# bot_schem_rev10.net
KiCad netlist of a schematic drawn in Altium Designer
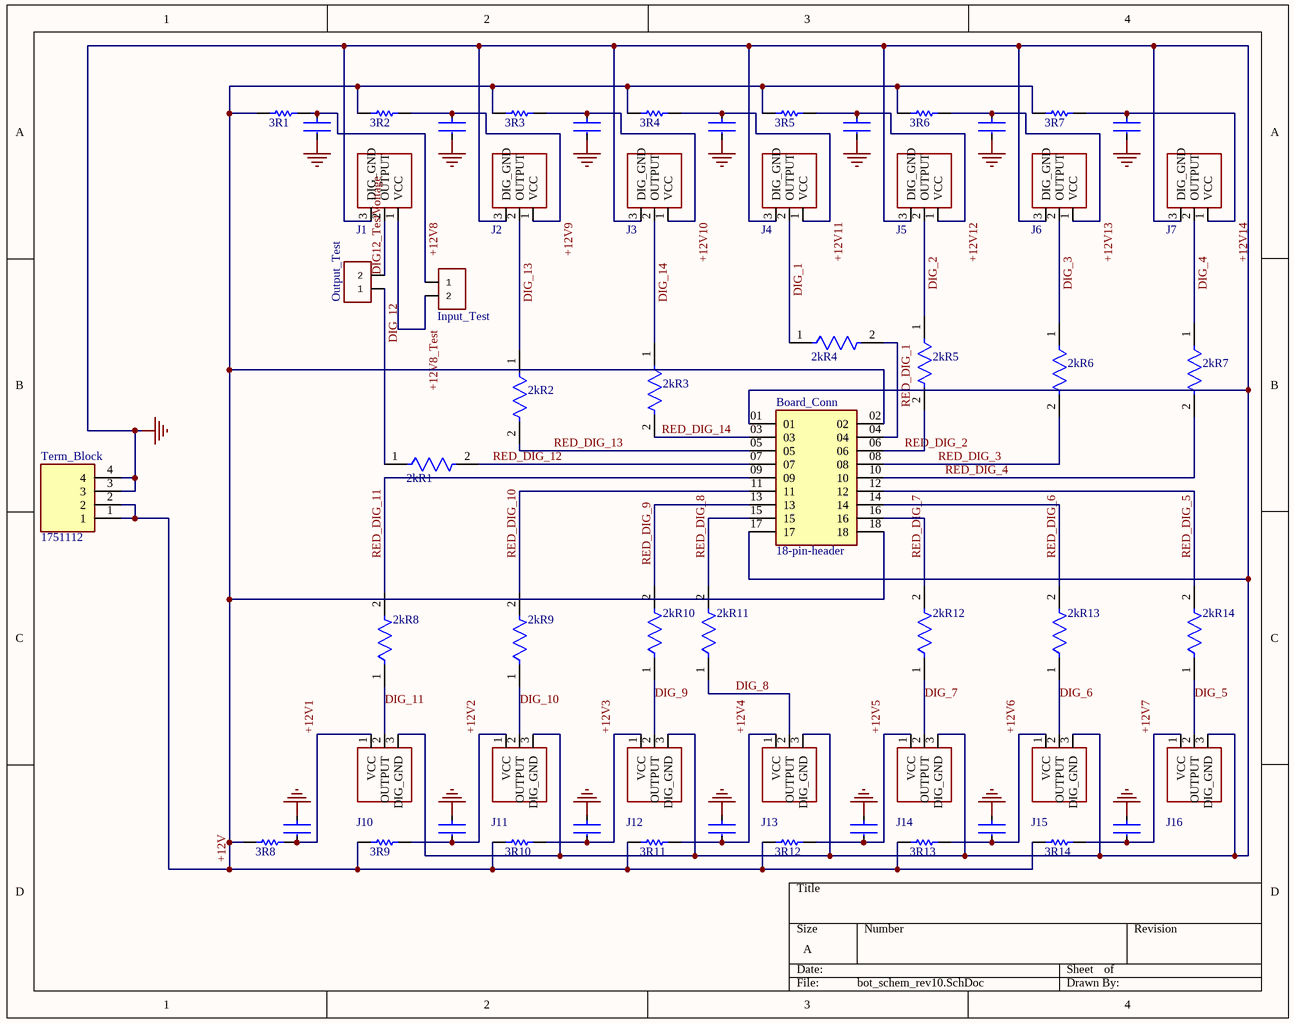
[diagram p0: bot_schem_rev10.SchDoc]

(export (version "E")
  (design (tool "Eeschema 10.0.6"))
  (components
    (comp (ref "2kR1")
      (value "CRCW06031K80FKEA")
      (footprint "2kOhm")
      (description "Res Thick Film 0603 1.8K Ohm 1% 1/10W ±100ppm/°C Molded SMD Paper T/R")
      (fields (field (name "MANUFACTURER") "Vishay") (field (name "TOLERANCE") "1%"))
      (libsource (lib "ps_schlib") (part "CRCW06031K80FKEA"))
    )
    (comp (ref "2kR2")
      (value "CRCW06031K80FKEA")
      (footprint "2kOhm")
      (description "Res Thick Film 0603 1.8K Ohm 1% 1/10W ±100ppm/°C Molded SMD Paper T/R")
      (fields (field (name "MANUFACTURER") "Vishay") (field (name "TOLERANCE") "1%"))
      (libsource (lib "ps_schlib") (part "CRCW06031K80FKEA"))
    )
    (comp (ref "2kR3")
      (value "CRCW06031K80FKEA")
      (footprint "2kOhm")
      (description "Res Thick Film 0603 1.8K Ohm 1% 1/10W ±100ppm/°C Molded SMD Paper T/R")
      (fields (field (name "MANUFACTURER") "Vishay") (field (name "TOLERANCE") "1%"))
      (libsource (lib "ps_schlib") (part "CRCW06031K80FKEA"))
    )
    (comp (ref "2kR4")
      (value "CRCW06031K80FKEA")
      (footprint "2kOhm")
      (description "Res Thick Film 0603 1.8K Ohm 1% 1/10W ±100ppm/°C Molded SMD Paper T/R")
      (fields (field (name "MANUFACTURER") "Vishay") (field (name "TOLERANCE") "1%"))
      (libsource (lib "ps_schlib") (part "CRCW06031K80FKEA"))
    )
    (comp (ref "2kR5")
      (value "CRCW06031K80FKEA")
      (footprint "2kOhm")
      (description "Res Thick Film 0603 1.8K Ohm 1% 1/10W ±100ppm/°C Molded SMD Paper T/R")
      (fields (field (name "MANUFACTURER") "Vishay") (field (name "TOLERANCE") "1%"))
      (libsource (lib "ps_schlib") (part "CRCW06031K80FKEA"))
    )
    (comp (ref "2kR6")
      (value "CRCW06031K80FKEA")
      (footprint "2kOhm")
      (description "Res Thick Film 0603 1.8K Ohm 1% 1/10W ±100ppm/°C Molded SMD Paper T/R")
      (fields (field (name "MANUFACTURER") "Vishay") (field (name "TOLERANCE") "1%"))
      (libsource (lib "ps_schlib") (part "CRCW06031K80FKEA"))
    )
    (comp (ref "2kR7")
      (value "CRCW06031K80FKEA")
      (footprint "2kOhm")
      (description "Res Thick Film 0603 1.8K Ohm 1% 1/10W ±100ppm/°C Molded SMD Paper T/R")
      (fields (field (name "MANUFACTURER") "Vishay") (field (name "TOLERANCE") "1%"))
      (libsource (lib "ps_schlib") (part "CRCW06031K80FKEA"))
    )
    (comp (ref "2kR8")
      (value "CRCW06031K80FKEA")
      (footprint "2kOhm")
      (description "Res Thick Film 0603 1.8K Ohm 1% 1/10W ±100ppm/°C Molded SMD Paper T/R")
      (fields (field (name "MANUFACTURER") "Vishay") (field (name "TOLERANCE") "1%"))
      (libsource (lib "ps_schlib") (part "CRCW06031K80FKEA"))
    )
    (comp (ref "2kR9")
      (value "CRCW06031K80FKEA")
      (footprint "2kOhm")
      (description "Res Thick Film 0603 1.8K Ohm 1% 1/10W ±100ppm/°C Molded SMD Paper T/R")
      (fields (field (name "MANUFACTURER") "Vishay") (field (name "TOLERANCE") "1%"))
      (libsource (lib "ps_schlib") (part "CRCW06031K80FKEA"))
    )
    (comp (ref "2kR10")
      (value "CRCW06031K80FKEA")
      (footprint "2kOhm")
      (description "Res Thick Film 0603 1.8K Ohm 1% 1/10W ±100ppm/°C Molded SMD Paper T/R")
      (fields (field (name "MANUFACTURER") "Vishay") (field (name "TOLERANCE") "1%"))
      (libsource (lib "ps_schlib") (part "CRCW06031K80FKEA"))
    )
    (comp (ref "2kR11")
      (value "CRCW06031K80FKEA")
      (footprint "2kOhm")
      (description "Res Thick Film 0603 1.8K Ohm 1% 1/10W ±100ppm/°C Molded SMD Paper T/R")
      (fields (field (name "MANUFACTURER") "Vishay") (field (name "TOLERANCE") "1%"))
      (libsource (lib "ps_schlib") (part "CRCW06031K80FKEA"))
    )
    (comp (ref "2kR12")
      (value "CRCW06031K80FKEA")
      (footprint "2kOhm")
      (description "Res Thick Film 0603 1.8K Ohm 1% 1/10W ±100ppm/°C Molded SMD Paper T/R")
      (fields (field (name "MANUFACTURER") "Vishay") (field (name "TOLERANCE") "1%"))
      (libsource (lib "ps_schlib") (part "CRCW06031K80FKEA"))
    )
    (comp (ref "2kR13")
      (value "CRCW06031K80FKEA")
      (footprint "2kOhm")
      (description "Res Thick Film 0603 1.8K Ohm 1% 1/10W ±100ppm/°C Molded SMD Paper T/R")
      (fields (field (name "MANUFACTURER") "Vishay") (field (name "TOLERANCE") "1%"))
      (libsource (lib "ps_schlib") (part "CRCW06031K80FKEA"))
    )
    (comp (ref "2kR14")
      (value "CRCW06031K80FKEA")
      (footprint "2kOhm")
      (description "Res Thick Film 0603 1.8K Ohm 1% 1/10W ±100ppm/°C Molded SMD Paper T/R")
      (fields (field (name "MANUFACTURER") "Vishay") (field (name "TOLERANCE") "1%"))
      (libsource (lib "ps_schlib") (part "CRCW06031K80FKEA"))
    )
    (comp (ref "3R1")
      (value "ERJ-2BQJR30X")
      (footprint "03 Ohm")
      (description "RES 0.3 OHM 5% 1/6W 0402")
      (fields (field (name "MANUFACTURER") "Panasonic") (field (name "TOLERANCE") "5%"))
      (libsource (lib "ps_schlib") (part "ERJ-2BQJR30X"))
    )
    (comp (ref "3R2")
      (value "ERJ-2BQJR30X")
      (footprint "03 Ohm")
      (description "RES 0.3 OHM 5% 1/6W 0402")
      (fields (field (name "MANUFACTURER") "Panasonic") (field (name "TOLERANCE") "5%"))
      (libsource (lib "ps_schlib") (part "ERJ-2BQJR30X"))
    )
    (comp (ref "3R3")
      (value "ERJ-2BQJR30X")
      (footprint "03 Ohm")
      (description "RES 0.3 OHM 5% 1/6W 0402")
      (fields (field (name "MANUFACTURER") "Panasonic") (field (name "TOLERANCE") "5%"))
      (libsource (lib "ps_schlib") (part "ERJ-2BQJR30X"))
    )
    (comp (ref "3R4")
      (value "ERJ-2BQJR30X")
      (footprint "03 Ohm")
      (description "RES 0.3 OHM 5% 1/6W 0402")
      (fields (field (name "MANUFACTURER") "Panasonic") (field (name "TOLERANCE") "5%"))
      (libsource (lib "ps_schlib") (part "ERJ-2BQJR30X"))
    )
    (comp (ref "3R5")
      (value "ERJ-2BQJR30X")
      (footprint "03 Ohm")
      (description "RES 0.3 OHM 5% 1/6W 0402")
      (fields (field (name "MANUFACTURER") "Panasonic") (field (name "TOLERANCE") "5%"))
      (libsource (lib "ps_schlib") (part "ERJ-2BQJR30X"))
    )
    (comp (ref "3R6")
      (value "ERJ-2BQJR30X")
      (footprint "03 Ohm")
      (description "RES 0.3 OHM 5% 1/6W 0402")
      (fields (field (name "MANUFACTURER") "Panasonic") (field (name "TOLERANCE") "5%"))
      (libsource (lib "ps_schlib") (part "ERJ-2BQJR30X"))
    )
    (comp (ref "3R7")
      (value "ERJ-2BQJR30X")
      (footprint "03 Ohm")
      (description "RES 0.3 OHM 5% 1/6W 0402")
      (fields (field (name "MANUFACTURER") "Panasonic") (field (name "TOLERANCE") "5%"))
      (libsource (lib "ps_schlib") (part "ERJ-2BQJR30X"))
    )
    (comp (ref "3R8")
      (value "ERJ-2BQJR30X")
      (footprint "03 Ohm")
      (description "RES 0.3 OHM 5% 1/6W 0402")
      (fields (field (name "MANUFACTURER") "Panasonic") (field (name "TOLERANCE") "5%"))
      (libsource (lib "ps_schlib") (part "ERJ-2BQJR30X"))
    )
    (comp (ref "3R9")
      (value "ERJ-2BQJR30X")
      (footprint "03 Ohm")
      (description "RES 0.3 OHM 5% 1/6W 0402")
      (fields (field (name "MANUFACTURER") "Panasonic") (field (name "TOLERANCE") "5%"))
      (libsource (lib "ps_schlib") (part "ERJ-2BQJR30X"))
    )
    (comp (ref "3R10")
      (value "ERJ-2BQJR30X")
      (footprint "03 Ohm")
      (description "RES 0.3 OHM 5% 1/6W 0402")
      (fields (field (name "MANUFACTURER") "Panasonic") (field (name "TOLERANCE") "5%"))
      (libsource (lib "ps_schlib") (part "ERJ-2BQJR30X"))
    )
    (comp (ref "3R11")
      (value "ERJ-2BQJR30X")
      (footprint "03 Ohm")
      (description "RES 0.3 OHM 5% 1/6W 0402")
      (fields (field (name "MANUFACTURER") "Panasonic") (field (name "TOLERANCE") "5%"))
      (libsource (lib "ps_schlib") (part "ERJ-2BQJR30X"))
    )
    (comp (ref "3R12")
      (value "ERJ-2BQJR30X")
      (footprint "03 Ohm")
      (description "RES 0.3 OHM 5% 1/6W 0402")
      (fields (field (name "MANUFACTURER") "Panasonic") (field (name "TOLERANCE") "5%"))
      (libsource (lib "ps_schlib") (part "ERJ-2BQJR30X"))
    )
    (comp (ref "3R13")
      (value "ERJ-2BQJR30X")
      (footprint "03 Ohm")
      (description "RES 0.3 OHM 5% 1/6W 0402")
      (fields (field (name "MANUFACTURER") "Panasonic") (field (name "TOLERANCE") "5%"))
      (libsource (lib "ps_schlib") (part "ERJ-2BQJR30X"))
    )
    (comp (ref "3R14")
      (value "ERJ-2BQJR30X")
      (footprint "03 Ohm")
      (description "RES 0.3 OHM 5% 1/6W 0402")
      (fields (field (name "MANUFACTURER") "Panasonic") (field (name "TOLERANCE") "5%"))
      (libsource (lib "ps_schlib") (part "ERJ-2BQJR30X"))
    )
    (comp (ref "Board_Conn")
      (value "18-pin-header")
      (footprint "18 pin header")
      (libsource (lib "bot_schlib") (part "18-pin-header"))
    )
    (comp (ref "C1")
      (value "C0805C104K5RACTU")
      (footprint "100nF")
      (description "Cap Ceramic 0.1uF 50V X7R 10% SMD 2.0 x 1.2 mm 125 C Paper T/R")
      (fields (field (name "MANUFACTURER") "KEMET") (field (name "TOLERANCE") "10%"))
      (libsource (lib "ps_schlib") (part "C0805C104K5RACTU"))
    )
    (comp (ref "C2")
      (value "C0805C104K5RACTU")
      (footprint "100nF")
      (description "Cap Ceramic 0.1uF 50V X7R 10% SMD 2.0 x 1.2 mm 125 C Paper T/R")
      (fields (field (name "MANUFACTURER") "KEMET") (field (name "TOLERANCE") "10%"))
      (libsource (lib "ps_schlib") (part "C0805C104K5RACTU"))
    )
    (comp (ref "C3")
      (value "C0805C104K5RACTU")
      (footprint "100nF")
      (description "Cap Ceramic 0.1uF 50V X7R 10% SMD 2.0 x 1.2 mm 125 C Paper T/R")
      (fields (field (name "MANUFACTURER") "KEMET") (field (name "TOLERANCE") "10%"))
      (libsource (lib "ps_schlib") (part "C0805C104K5RACTU"))
    )
    (comp (ref "C4")
      (value "C0805C104K5RACTU")
      (footprint "100nF")
      (description "Cap Ceramic 0.1uF 50V X7R 10% SMD 2.0 x 1.2 mm 125 C Paper T/R")
      (fields (field (name "MANUFACTURER") "KEMET") (field (name "TOLERANCE") "10%"))
      (libsource (lib "ps_schlib") (part "C0805C104K5RACTU"))
    )
    (comp (ref "C5")
      (value "C0805C104K5RACTU")
      (footprint "100nF")
      (description "Cap Ceramic 0.1uF 50V X7R 10% SMD 2.0 x 1.2 mm 125 C Paper T/R")
      (fields (field (name "MANUFACTURER") "KEMET") (field (name "TOLERANCE") "10%"))
      (libsource (lib "ps_schlib") (part "C0805C104K5RACTU"))
    )
    (comp (ref "C6")
      (value "C0805C104K5RACTU")
      (footprint "100nF")
      (description "Cap Ceramic 0.1uF 50V X7R 10% SMD 2.0 x 1.2 mm 125 C Paper T/R")
      (fields (field (name "MANUFACTURER") "KEMET") (field (name "TOLERANCE") "10%"))
      (libsource (lib "ps_schlib") (part "C0805C104K5RACTU"))
    )
    (comp (ref "C7")
      (value "C0805C104K5RACTU")
      (footprint "100nF")
      (description "Cap Ceramic 0.1uF 50V X7R 10% SMD 2.0 x 1.2 mm 125 C Paper T/R")
      (fields (field (name "MANUFACTURER") "KEMET") (field (name "TOLERANCE") "10%"))
      (libsource (lib "ps_schlib") (part "C0805C104K5RACTU"))
    )
    (comp (ref "C8")
      (value "C0805C104K5RACTU")
      (footprint "100nF")
      (description "Cap Ceramic 0.1uF 50V X7R 10% SMD 2.0 x 1.2 mm 125 C Paper T/R")
      (fields (field (name "MANUFACTURER") "KEMET") (field (name "TOLERANCE") "10%"))
      (libsource (lib "ps_schlib") (part "C0805C104K5RACTU"))
    )
    (comp (ref "C9")
      (value "C0805C104K5RACTU")
      (footprint "100nF")
      (description "Cap Ceramic 0.1uF 50V X7R 10% SMD 2.0 x 1.2 mm 125 C Paper T/R")
      (fields (field (name "MANUFACTURER") "KEMET") (field (name "TOLERANCE") "10%"))
      (libsource (lib "ps_schlib") (part "C0805C104K5RACTU"))
    )
    (comp (ref "C10")
      (value "C0805C104K5RACTU")
      (footprint "100nF")
      (description "Cap Ceramic 0.1uF 50V X7R 10% SMD 2.0 x 1.2 mm 125 C Paper T/R")
      (fields (field (name "MANUFACTURER") "KEMET") (field (name "TOLERANCE") "10%"))
      (libsource (lib "ps_schlib") (part "C0805C104K5RACTU"))
    )
    (comp (ref "C11")
      (value "C0805C104K5RACTU")
      (footprint "100nF")
      (description "Cap Ceramic 0.1uF 50V X7R 10% SMD 2.0 x 1.2 mm 125 C Paper T/R")
      (fields (field (name "MANUFACTURER") "KEMET") (field (name "TOLERANCE") "10%"))
      (libsource (lib "ps_schlib") (part "C0805C104K5RACTU"))
    )
    (comp (ref "C12")
      (value "C0805C104K5RACTU")
      (footprint "100nF")
      (description "Cap Ceramic 0.1uF 50V X7R 10% SMD 2.0 x 1.2 mm 125 C Paper T/R")
      (fields (field (name "MANUFACTURER") "KEMET") (field (name "TOLERANCE") "10%"))
      (libsource (lib "ps_schlib") (part "C0805C104K5RACTU"))
    )
    (comp (ref "C13")
      (value "C0805C104K5RACTU")
      (footprint "100nF")
      (description "Cap Ceramic 0.1uF 50V X7R 10% SMD 2.0 x 1.2 mm 125 C Paper T/R")
      (fields (field (name "MANUFACTURER") "KEMET") (field (name "TOLERANCE") "10%"))
      (libsource (lib "ps_schlib") (part "C0805C104K5RACTU"))
    )
    (comp (ref "C14")
      (value "C0805C104K5RACTU")
      (footprint "100nF")
      (description "Cap Ceramic 0.1uF 50V X7R 10% SMD 2.0 x 1.2 mm 125 C Paper T/R")
      (fields (field (name "MANUFACTURER") "KEMET") (field (name "TOLERANCE") "10%"))
      (libsource (lib "ps_schlib") (part "C0805C104K5RACTU"))
    )
    (comp (ref "Input_Test")
      (value "PRPC001DFAN-RC")
      (footprint "PRPC001DFAN-RC")
      (description "Conn Header Vert 2POS")
      (fields (field (name "MANUFACTURER") "Sullins"))
      (libsource (lib "ps_schlib") (part "PRPC001DFAN-RC"))
    )
    (comp (ref "J1")
      (value "IF-D95T")
      (footprint "IF-D95")
      (description "DETECTOR PHOTOLOGIC TTL/CMOS")
      (fields (field (name "MANUFACTURER") "Industrial Fiber Optics"))
      (libsource (lib "ps_schlib") (part "IF-D95T"))
    )
    (comp (ref "J2")
      (value "IF-D95T")
      (footprint "IF-D95")
      (description "DETECTOR PHOTOLOGIC TTL/CMOS")
      (fields (field (name "MANUFACTURER") "Industrial Fiber Optics"))
      (libsource (lib "ps_schlib") (part "IF-D95T"))
    )
    (comp (ref "J3")
      (value "IF-D95T")
      (footprint "IF-D95")
      (description "DETECTOR PHOTOLOGIC TTL/CMOS")
      (fields (field (name "MANUFACTURER") "Industrial Fiber Optics"))
      (libsource (lib "ps_schlib") (part "IF-D95T"))
    )
    (comp (ref "J4")
      (value "IF-D95T")
      (footprint "IF-D95")
      (description "DETECTOR PHOTOLOGIC TTL/CMOS")
      (fields (field (name "MANUFACTURER") "Industrial Fiber Optics"))
      (libsource (lib "ps_schlib") (part "IF-D95T"))
    )
    (comp (ref "J5")
      (value "IF-D95T")
      (footprint "IF-D95")
      (description "DETECTOR PHOTOLOGIC TTL/CMOS")
      (fields (field (name "MANUFACTURER") "Industrial Fiber Optics"))
      (libsource (lib "ps_schlib") (part "IF-D95T"))
    )
    (comp (ref "J6")
      (value "IF-D95T")
      (footprint "IF-D95")
      (description "DETECTOR PHOTOLOGIC TTL/CMOS")
      (fields (field (name "MANUFACTURER") "Industrial Fiber Optics"))
      (libsource (lib "ps_schlib") (part "IF-D95T"))
    )
    (comp (ref "J7")
      (value "IF-D95T")
      (footprint "IF-D95")
      (description "DETECTOR PHOTOLOGIC TTL/CMOS")
      (fields (field (name "MANUFACTURER") "Industrial Fiber Optics"))
      (libsource (lib "ps_schlib") (part "IF-D95T"))
    )
    (comp (ref "J10")
      (value "IF-D95T")
      (footprint "IF-D95")
      (description "DETECTOR PHOTOLOGIC TTL/CMOS")
      (fields (field (name "MANUFACTURER") "Industrial Fiber Optics"))
      (libsource (lib "ps_schlib") (part "IF-D95T"))
    )
    (comp (ref "J11")
      (value "IF-D95T")
      (footprint "IF-D95")
      (description "DETECTOR PHOTOLOGIC TTL/CMOS")
      (fields (field (name "MANUFACTURER") "Industrial Fiber Optics"))
      (libsource (lib "ps_schlib") (part "IF-D95T"))
    )
    (comp (ref "J12")
      (value "IF-D95T")
      (footprint "IF-D95")
      (description "DETECTOR PHOTOLOGIC TTL/CMOS")
      (fields (field (name "MANUFACTURER") "Industrial Fiber Optics"))
      (libsource (lib "ps_schlib") (part "IF-D95T"))
    )
    (comp (ref "J13")
      (value "IF-D95T")
      (footprint "IF-D95")
      (description "DETECTOR PHOTOLOGIC TTL/CMOS")
      (fields (field (name "MANUFACTURER") "Industrial Fiber Optics"))
      (libsource (lib "ps_schlib") (part "IF-D95T"))
    )
    (comp (ref "J14")
      (value "IF-D95T")
      (footprint "IF-D95")
      (description "DETECTOR PHOTOLOGIC TTL/CMOS")
      (fields (field (name "MANUFACTURER") "Industrial Fiber Optics"))
      (libsource (lib "ps_schlib") (part "IF-D95T"))
    )
    (comp (ref "J15")
      (value "IF-D95T")
      (footprint "IF-D95")
      (description "DETECTOR PHOTOLOGIC TTL/CMOS")
      (fields (field (name "MANUFACTURER") "Industrial Fiber Optics"))
      (libsource (lib "ps_schlib") (part "IF-D95T"))
    )
    (comp (ref "J16")
      (value "IF-D95T")
      (footprint "IF-D95")
      (description "DETECTOR PHOTOLOGIC TTL/CMOS")
      (fields (field (name "MANUFACTURER") "Industrial Fiber Optics"))
      (libsource (lib "ps_schlib") (part "IF-D95T"))
    )
    (comp (ref "Output_Test")
      (value "PRPC001DFAN-RC")
      (footprint "PRPC001DFAN-RC")
      (description "Conn Header Vert 2POS")
      (fields (field (name "MANUFACTURER") "Sullins"))
      (libsource (lib "ps_schlib") (part "PRPC001DFAN-RC"))
    )
    (comp (ref "Term_Block")
      (value "1751112")
      (footprint "SamacSys:1751112")
      (description "Connector")
      (libsource (lib "*") (part "1751112"))
    )
  )
  (nets
    (net (code "1") (name "/+12V") (class "Default")
      (node (ref "3R1") (pin "1") (pinfunction "1_1") (pintype "passive"))
      (node (ref "3R10") (pin "1") (pinfunction "1_1") (pintype "passive"))
      (node (ref "3R11") (pin "1") (pinfunction "1_1") (pintype "passive"))
      (node (ref "3R12") (pin "1") (pinfunction "1_1") (pintype "passive"))
      (node (ref "3R13") (pin "1") (pinfunction "1_1") (pintype "passive"))
      (node (ref "3R14") (pin "1") (pinfunction "1_1") (pintype "passive"))
      (node (ref "3R2") (pin "1") (pinfunction "1_1") (pintype "passive"))
      (node (ref "3R3") (pin "1") (pinfunction "1_1") (pintype "passive"))
      (node (ref "3R4") (pin "1") (pinfunction "1_1") (pintype "passive"))
      (node (ref "3R5") (pin "1") (pinfunction "1_1") (pintype "passive"))
      (node (ref "3R6") (pin "1") (pinfunction "1_1") (pintype "passive"))
      (node (ref "3R7") (pin "1") (pinfunction "1_1") (pintype "passive"))
      (node (ref "3R8") (pin "1") (pinfunction "1_1") (pintype "passive"))
      (node (ref "3R9") (pin "1") (pinfunction "1_1") (pintype "passive"))
      (node (ref "Board_Conn") (pin "02") (pinfunction "02_02") (pintype "passive"))
      (node (ref "Board_Conn") (pin "18") (pinfunction "18_18") (pintype "passive"))
      (node (ref "Term_Block") (pin "1") (pinfunction "1_1") (pintype "passive"))
      (node (ref "Term_Block") (pin "2") (pinfunction "2_2") (pintype "passive"))
    )
    (net (code "2") (name "/+12V1") (class "Default")
      (node (ref "3R8") (pin "2") (pinfunction "2_2") (pintype "passive"))
      (node (ref "C8") (pin "2") (pinfunction "2_2") (pintype "passive"))
      (node (ref "J10") (pin "1") (pinfunction "VCC_1") (pintype "passive"))
    )
    (net (code "3") (name "/+12V2") (class "Default")
      (node (ref "3R9") (pin "2") (pinfunction "2_2") (pintype "passive"))
      (node (ref "C9") (pin "2") (pinfunction "2_2") (pintype "passive"))
      (node (ref "J11") (pin "1") (pinfunction "VCC_1") (pintype "passive"))
    )
    (net (code "4") (name "/+12V3") (class "Default")
      (node (ref "3R10") (pin "2") (pinfunction "2_2") (pintype "passive"))
      (node (ref "C10") (pin "2") (pinfunction "2_2") (pintype "passive"))
      (node (ref "J12") (pin "1") (pinfunction "VCC_1") (pintype "passive"))
    )
    (net (code "5") (name "/+12V4") (class "Default")
      (node (ref "3R11") (pin "2") (pinfunction "2_2") (pintype "passive"))
      (node (ref "C11") (pin "2") (pinfunction "2_2") (pintype "passive"))
      (node (ref "J13") (pin "1") (pinfunction "VCC_1") (pintype "passive"))
    )
    (net (code "6") (name "/+12V5") (class "Default")
      (node (ref "3R12") (pin "2") (pinfunction "2_2") (pintype "passive"))
      (node (ref "C12") (pin "2") (pinfunction "2_2") (pintype "passive"))
      (node (ref "J14") (pin "1") (pinfunction "VCC_1") (pintype "passive"))
    )
    (net (code "7") (name "/+12V6") (class "Default")
      (node (ref "3R13") (pin "2") (pinfunction "2_2") (pintype "passive"))
      (node (ref "C13") (pin "2") (pinfunction "2_2") (pintype "passive"))
      (node (ref "J15") (pin "1") (pinfunction "VCC_1") (pintype "passive"))
    )
    (net (code "8") (name "/+12V7") (class "Default")
      (node (ref "3R14") (pin "2") (pinfunction "2_2") (pintype "passive"))
      (node (ref "C14") (pin "2") (pinfunction "2_2") (pintype "passive"))
      (node (ref "J16") (pin "1") (pinfunction "VCC_1") (pintype "passive"))
    )
    (net (code "9") (name "/+12V8") (class "Default")
      (node (ref "3R1") (pin "2") (pinfunction "2_2") (pintype "passive"))
      (node (ref "C1") (pin "1") (pinfunction "1_1") (pintype "passive"))
      (node (ref "Input_Test") (pin "1") (pinfunction "1_1") (pintype "passive"))
    )
    (net (code "10") (name "/+12V8_Test") (class "Default")
      (node (ref "Input_Test") (pin "2") (pinfunction "2_2") (pintype "passive"))
      (node (ref "J1") (pin "1") (pinfunction "VCC_1") (pintype "passive"))
    )
    (net (code "11") (name "/+12V9") (class "Default")
      (node (ref "3R2") (pin "2") (pinfunction "2_2") (pintype "passive"))
      (node (ref "C2") (pin "1") (pinfunction "1_1") (pintype "passive"))
      (node (ref "J2") (pin "1") (pinfunction "VCC_1") (pintype "passive"))
    )
    (net (code "12") (name "/+12V10") (class "Default")
      (node (ref "3R3") (pin "2") (pinfunction "2_2") (pintype "passive"))
      (node (ref "C3") (pin "1") (pinfunction "1_1") (pintype "passive"))
      (node (ref "J3") (pin "1") (pinfunction "VCC_1") (pintype "passive"))
    )
    (net (code "13") (name "/+12V11") (class "Default")
      (node (ref "3R4") (pin "2") (pinfunction "2_2") (pintype "passive"))
      (node (ref "C4") (pin "1") (pinfunction "1_1") (pintype "passive"))
      (node (ref "J4") (pin "1") (pinfunction "VCC_1") (pintype "passive"))
    )
    (net (code "14") (name "/+12V12") (class "Default")
      (node (ref "3R5") (pin "2") (pinfunction "2_2") (pintype "passive"))
      (node (ref "C5") (pin "1") (pinfunction "1_1") (pintype "passive"))
      (node (ref "J5") (pin "1") (pinfunction "VCC_1") (pintype "passive"))
    )
    (net (code "15") (name "/+12V13") (class "Default")
      (node (ref "3R6") (pin "2") (pinfunction "2_2") (pintype "passive"))
      (node (ref "C6") (pin "1") (pinfunction "1_1") (pintype "passive"))
      (node (ref "J6") (pin "1") (pinfunction "VCC_1") (pintype "passive"))
    )
    (net (code "16") (name "/+12V14") (class "Default")
      (node (ref "3R7") (pin "2") (pinfunction "2_2") (pintype "passive"))
      (node (ref "C7") (pin "1") (pinfunction "1_1") (pintype "passive"))
      (node (ref "J7") (pin "1") (pinfunction "VCC_1") (pintype "passive"))
    )
    (net (code "18") (name "/DIG12_TestVoltage") (class "Default")
      (node (ref "J1") (pin "2") (pinfunction "OUTPUT_2") (pintype "passive"))
      (node (ref "Output_Test") (pin "2") (pinfunction "2_2") (pintype "passive"))
    )
    (net (code "19") (name "/DIG_1") (class "Default")
      (node (ref "2kR4") (pin "1") (pinfunction "1_1") (pintype "passive"))
      (node (ref "J4") (pin "2") (pinfunction "OUTPUT_2") (pintype "passive"))
    )
    (net (code "20") (name "/DIG_2") (class "Default")
      (node (ref "2kR5") (pin "1") (pinfunction "1_1") (pintype "passive"))
      (node (ref "J5") (pin "2") (pinfunction "OUTPUT_2") (pintype "passive"))
    )
    (net (code "21") (name "/DIG_3") (class "Default")
      (node (ref "2kR6") (pin "1") (pinfunction "1_1") (pintype "passive"))
      (node (ref "J6") (pin "2") (pinfunction "OUTPUT_2") (pintype "passive"))
    )
    (net (code "22") (name "/DIG_4") (class "Default")
      (node (ref "2kR7") (pin "1") (pinfunction "1_1") (pintype "passive"))
      (node (ref "J7") (pin "2") (pinfunction "OUTPUT_2") (pintype "passive"))
    )
    (net (code "23") (name "/DIG_5") (class "Default")
      (node (ref "2kR14") (pin "1") (pinfunction "1_1") (pintype "passive"))
      (node (ref "J16") (pin "2") (pinfunction "OUTPUT_2") (pintype "passive"))
    )
    (net (code "24") (name "/DIG_6") (class "Default")
      (node (ref "2kR13") (pin "1") (pinfunction "1_1") (pintype "passive"))
      (node (ref "J15") (pin "2") (pinfunction "OUTPUT_2") (pintype "passive"))
    )
    (net (code "25") (name "/DIG_7") (class "Default")
      (node (ref "2kR12") (pin "1") (pinfunction "1_1") (pintype "passive"))
      (node (ref "J14") (pin "2") (pinfunction "OUTPUT_2") (pintype "passive"))
    )
    (net (code "26") (name "/DIG_8") (class "Default")
      (node (ref "2kR11") (pin "1") (pinfunction "1_1") (pintype "passive"))
      (node (ref "J13") (pin "2") (pinfunction "OUTPUT_2") (pintype "passive"))
    )
    (net (code "27") (name "/DIG_9") (class "Default")
      (node (ref "2kR10") (pin "1") (pinfunction "1_1") (pintype "passive"))
      (node (ref "J12") (pin "2") (pinfunction "OUTPUT_2") (pintype "passive"))
    )
    (net (code "28") (name "/DIG_10") (class "Default")
      (node (ref "2kR9") (pin "1") (pinfunction "1_1") (pintype "passive"))
      (node (ref "J11") (pin "2") (pinfunction "OUTPUT_2") (pintype "passive"))
    )
    (net (code "29") (name "/DIG_11") (class "Default")
      (node (ref "2kR8") (pin "1") (pinfunction "1_1") (pintype "passive"))
      (node (ref "J10") (pin "2") (pinfunction "OUTPUT_2") (pintype "passive"))
    )
    (net (code "30") (name "/DIG_12") (class "Default")
      (node (ref "2kR1") (pin "1") (pinfunction "1_1") (pintype "passive"))
      (node (ref "Output_Test") (pin "1") (pinfunction "1_1") (pintype "passive"))
    )
    (net (code "31") (name "/DIG_13") (class "Default")
      (node (ref "2kR2") (pin "1") (pinfunction "1_1") (pintype "passive"))
      (node (ref "J2") (pin "2") (pinfunction "OUTPUT_2") (pintype "passive"))
    )
    (net (code "32") (name "/DIG_14") (class "Default")
      (node (ref "2kR3") (pin "1") (pinfunction "1_1") (pintype "passive"))
      (node (ref "J3") (pin "2") (pinfunction "OUTPUT_2") (pintype "passive"))
    )
    (net (code "33") (name "/RED_DIG_1") (class "Default")
      (node (ref "2kR4") (pin "2") (pinfunction "2_2") (pintype "passive"))
      (node (ref "Board_Conn") (pin "04") (pinfunction "04_04") (pintype "passive"))
    )
    (net (code "34") (name "/RED_DIG_2") (class "Default")
      (node (ref "2kR5") (pin "2") (pinfunction "2_2") (pintype "passive"))
      (node (ref "Board_Conn") (pin "06") (pinfunction "06_06") (pintype "passive"))
    )
    (net (code "35") (name "/RED_DIG_3") (class "Default")
      (node (ref "2kR6") (pin "2") (pinfunction "2_2") (pintype "passive"))
      (node (ref "Board_Conn") (pin "08") (pinfunction "08_08") (pintype "passive"))
    )
    (net (code "36") (name "/RED_DIG_4") (class "Default")
      (node (ref "2kR7") (pin "2") (pinfunction "2_2") (pintype "passive"))
      (node (ref "Board_Conn") (pin "10") (pinfunction "10_10") (pintype "passive"))
    )
    (net (code "37") (name "/RED_DIG_5") (class "Default")
      (node (ref "2kR14") (pin "2") (pinfunction "2_2") (pintype "passive"))
      (node (ref "Board_Conn") (pin "12") (pinfunction "12_12") (pintype "passive"))
    )
    (net (code "38") (name "/RED_DIG_6") (class "Default")
      (node (ref "2kR13") (pin "2") (pinfunction "2_2") (pintype "passive"))
      (node (ref "Board_Conn") (pin "14") (pinfunction "14_14") (pintype "passive"))
    )
    (net (code "39") (name "/RED_DIG_7") (class "Default")
      (node (ref "2kR12") (pin "2") (pinfunction "2_2") (pintype "passive"))
      (node (ref "Board_Conn") (pin "16") (pinfunction "16_16") (pintype "passive"))
    )
    (net (code "40") (name "/RED_DIG_8") (class "Default")
      (node (ref "2kR11") (pin "2") (pinfunction "2_2") (pintype "passive"))
      (node (ref "Board_Conn") (pin "15") (pinfunction "15_15") (pintype "passive"))
    )
    (net (code "41") (name "/RED_DIG_9") (class "Default")
      (node (ref "2kR10") (pin "2") (pinfunction "2_2") (pintype "passive"))
      (node (ref "Board_Conn") (pin "13") (pinfunction "13_13") (pintype "passive"))
    )
    (net (code "42") (name "/RED_DIG_10") (class "Default")
      (node (ref "2kR9") (pin "2") (pinfunction "2_2") (pintype "passive"))
      (node (ref "Board_Conn") (pin "11") (pinfunction "11_11") (pintype "passive"))
    )
    (net (code "43") (name "/RED_DIG_11") (class "Default")
      (node (ref "2kR8") (pin "2") (pinfunction "2_2") (pintype "passive"))
      (node (ref "Board_Conn") (pin "09") (pinfunction "09_09") (pintype "passive"))
    )
    (net (code "44") (name "/RED_DIG_12") (class "Default")
      (node (ref "2kR1") (pin "2") (pinfunction "2_2") (pintype "passive"))
      (node (ref "Board_Conn") (pin "07") (pinfunction "07_07") (pintype "passive"))
    )
    (net (code "45") (name "/RED_DIG_13") (class "Default")
      (node (ref "2kR2") (pin "2") (pinfunction "2_2") (pintype "passive"))
      (node (ref "Board_Conn") (pin "05") (pinfunction "05_05") (pintype "passive"))
    )
    (net (code "46") (name "/RED_DIG_14") (class "Default")
      (node (ref "2kR3") (pin "2") (pinfunction "2_2") (pintype "passive"))
      (node (ref "Board_Conn") (pin "03") (pinfunction "03_03") (pintype "passive"))
    )
    (net (code "47") (name "GND") (class "Default")
      (node (ref "Board_Conn") (pin "01") (pinfunction "01_01") (pintype "passive"))
      (node (ref "Board_Conn") (pin "17") (pinfunction "17_17") (pintype "passive"))
      (node (ref "C1") (pin "2") (pinfunction "2_2") (pintype "passive"))
      (node (ref "C10") (pin "1") (pinfunction "1_1") (pintype "passive"))
      (node (ref "C11") (pin "1") (pinfunction "1_1") (pintype "passive"))
      (node (ref "C12") (pin "1") (pinfunction "1_1") (pintype "passive"))
      (node (ref "C13") (pin "1") (pinfunction "1_1") (pintype "passive"))
      (node (ref "C14") (pin "1") (pinfunction "1_1") (pintype "passive"))
      (node (ref "C2") (pin "2") (pinfunction "2_2") (pintype "passive"))
      (node (ref "C3") (pin "2") (pinfunction "2_2") (pintype "passive"))
      (node (ref "C4") (pin "2") (pinfunction "2_2") (pintype "passive"))
      (node (ref "C5") (pin "2") (pinfunction "2_2") (pintype "passive"))
      (node (ref "C6") (pin "2") (pinfunction "2_2") (pintype "passive"))
      (node (ref "C7") (pin "2") (pinfunction "2_2") (pintype "passive"))
      (node (ref "C8") (pin "1") (pinfunction "1_1") (pintype "passive"))
      (node (ref "C9") (pin "1") (pinfunction "1_1") (pintype "passive"))
      (node (ref "J1") (pin "3") (pinfunction "DIG_GND_3") (pintype "passive"))
      (node (ref "J10") (pin "3") (pinfunction "DIG_GND_3") (pintype "passive"))
      (node (ref "J11") (pin "3") (pinfunction "DIG_GND_3") (pintype "passive"))
      (node (ref "J12") (pin "3") (pinfunction "DIG_GND_3") (pintype "passive"))
      (node (ref "J13") (pin "3") (pinfunction "DIG_GND_3") (pintype "passive"))
      (node (ref "J14") (pin "3") (pinfunction "DIG_GND_3") (pintype "passive"))
      (node (ref "J15") (pin "3") (pinfunction "DIG_GND_3") (pintype "passive"))
      (node (ref "J16") (pin "3") (pinfunction "DIG_GND_3") (pintype "passive"))
      (node (ref "J2") (pin "3") (pinfunction "DIG_GND_3") (pintype "passive"))
      (node (ref "J3") (pin "3") (pinfunction "DIG_GND_3") (pintype "passive"))
      (node (ref "J4") (pin "3") (pinfunction "DIG_GND_3") (pintype "passive"))
      (node (ref "J5") (pin "3") (pinfunction "DIG_GND_3") (pintype "passive"))
      (node (ref "J6") (pin "3") (pinfunction "DIG_GND_3") (pintype "passive"))
      (node (ref "J7") (pin "3") (pinfunction "DIG_GND_3") (pintype "passive"))
      (node (ref "Term_Block") (pin "3") (pinfunction "3_3") (pintype "passive"))
      (node (ref "Term_Block") (pin "4") (pinfunction "4_4") (pintype "passive"))
    )
  )
)
